# Schematic_WT-03_v_1_0.net
KiCad netlist of a schematic drawn in EasyEDA
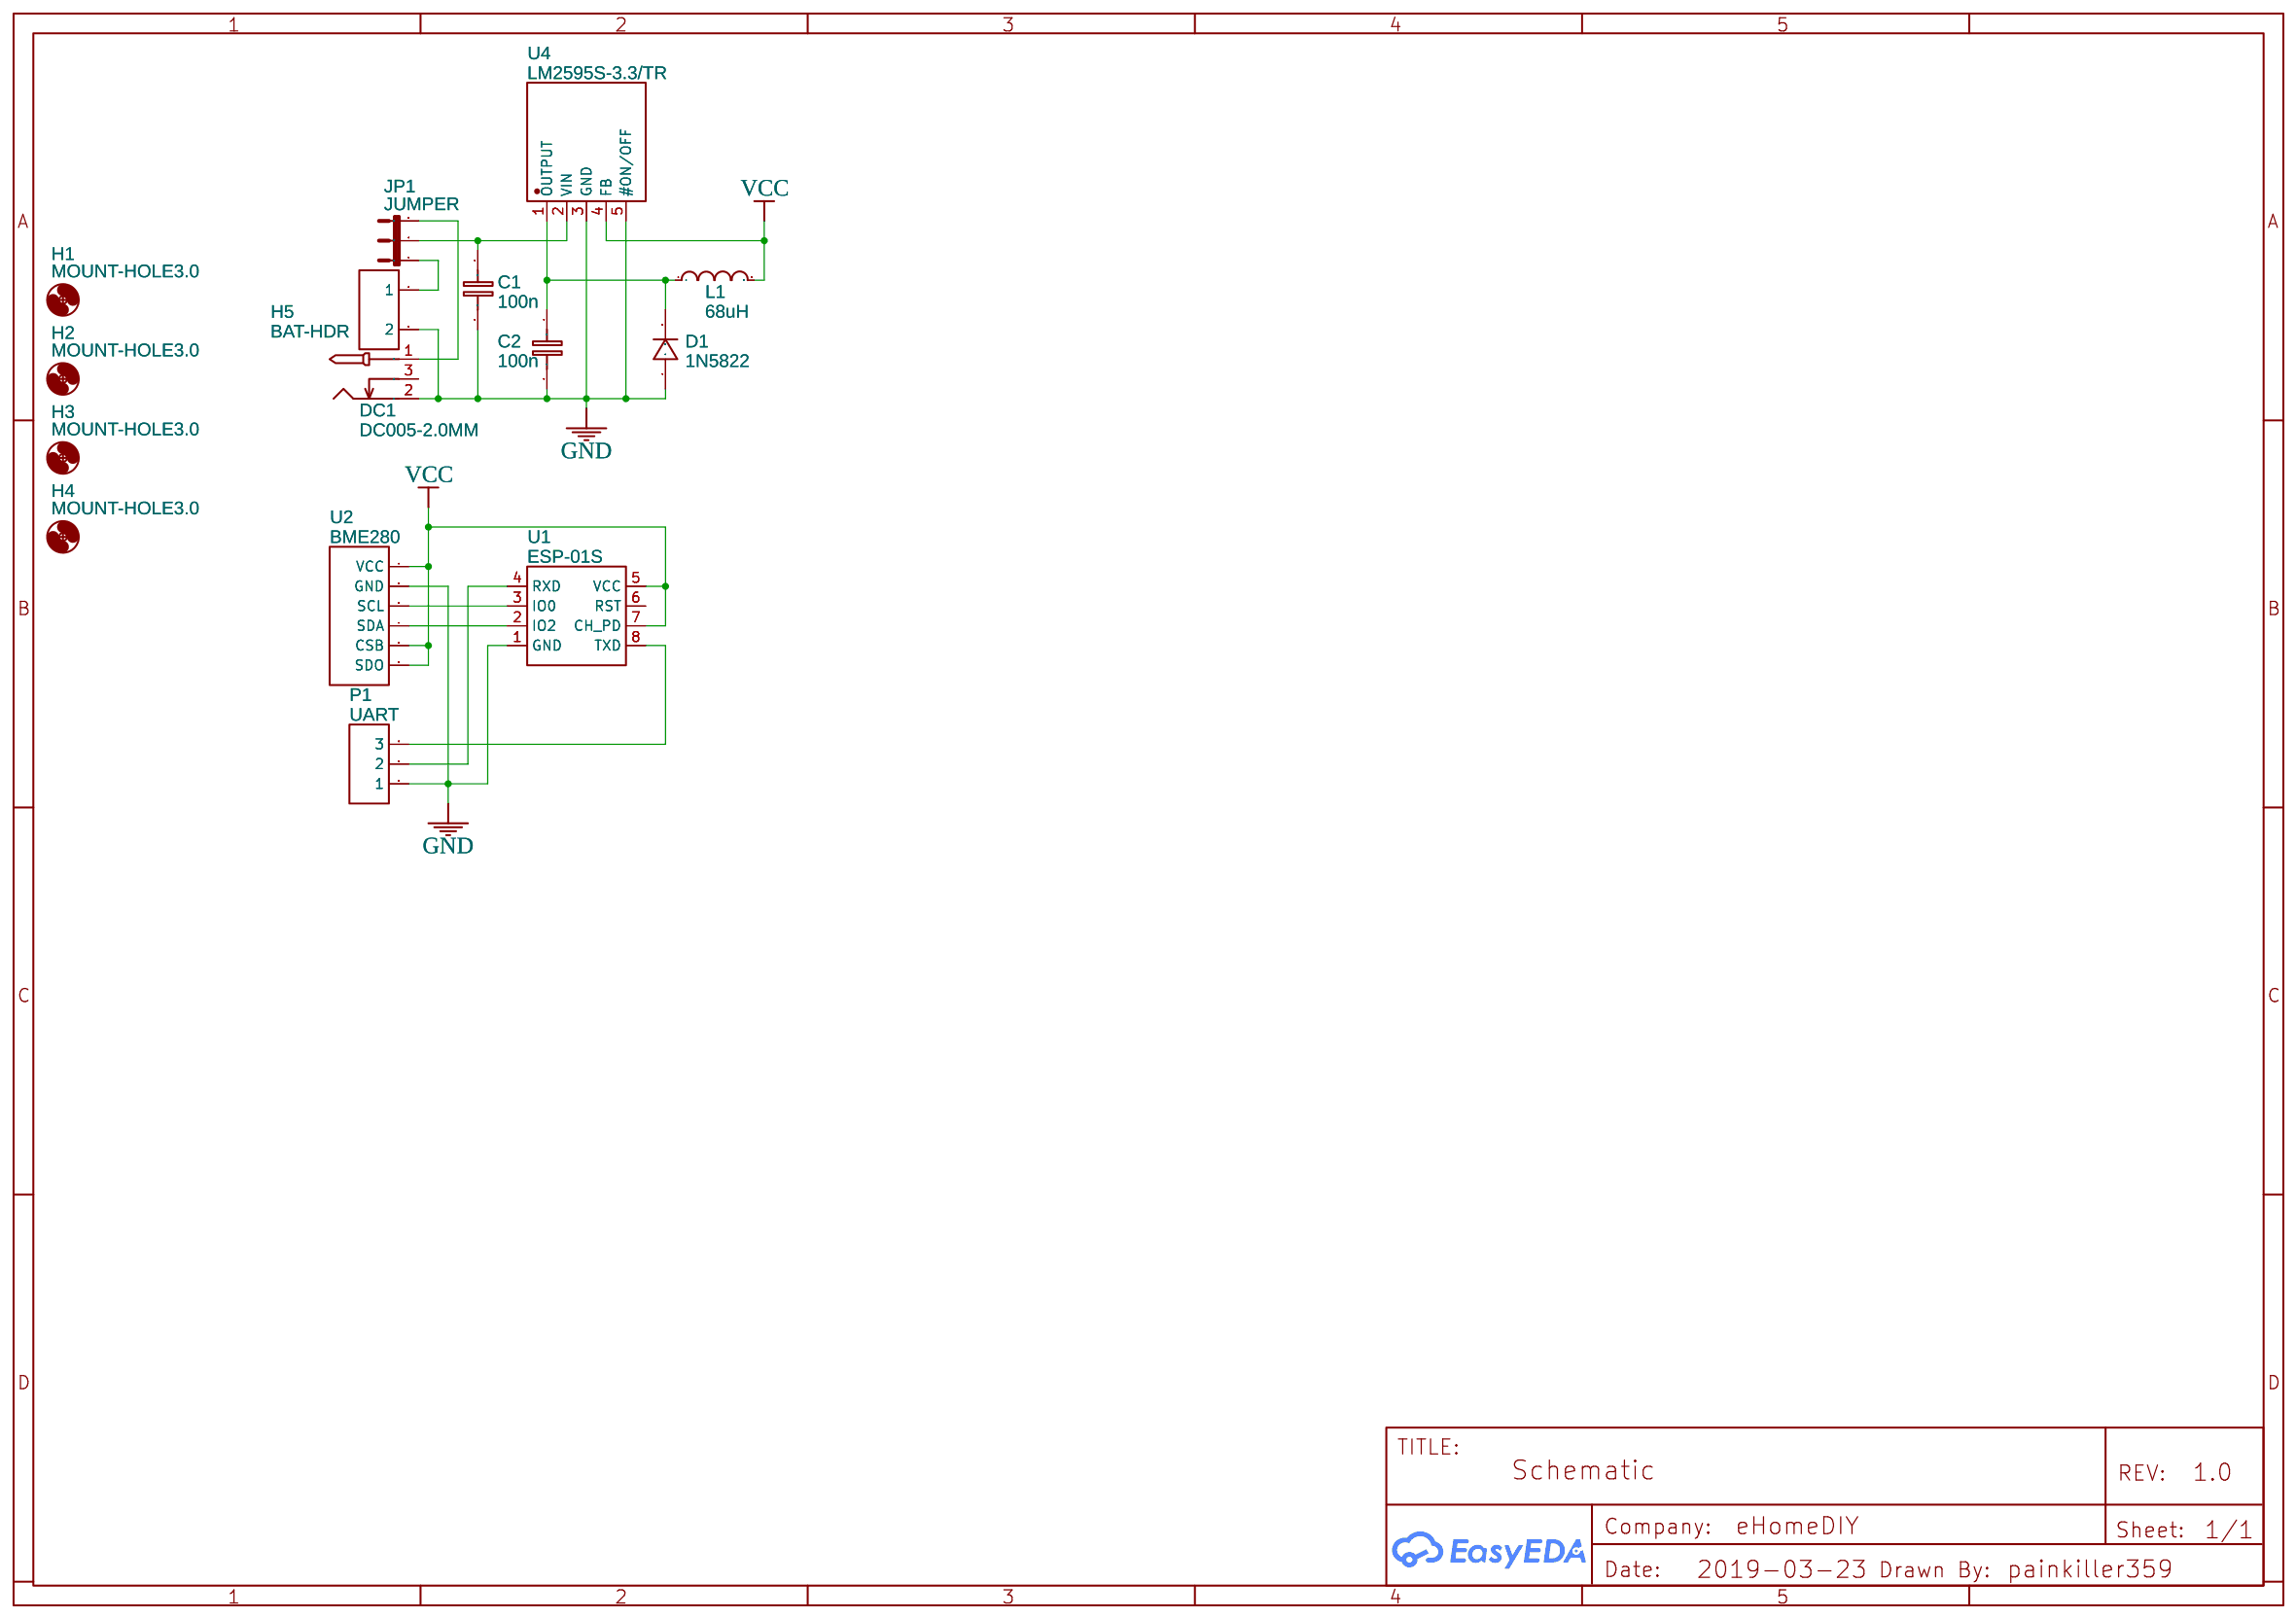
[diagram p0: schematic sheet]

(export (version "E")
  (design (tool "Eeschema 10.0.6"))
  (components
    (comp (ref "C1")
      (value "100n")
      (fields (field (name "BOM_Manufacturer Part") "?"))
      (libsource (lib "") (part "Cap_RAD-0.1_EU"))
    )
    (comp (ref "C2")
      (value "100n")
      (fields (field (name "BOM_Manufacturer Part") "?"))
      (libsource (lib "") (part "Cap_RAD-0.1_EU"))
    )
    (comp (ref "D1")
      (value "1N5822")
      (fields (field (name "BOM_Supplier Part") "C169161"))
      (libsource (lib "") (part "Unknown_330_170"))
    )
    (comp (ref "DC1")
      (value "DC005-2.0MM")
      (fields (field (name "BOM_Supplier Part") "C111567"))
      (libsource (lib "") (part "Unknown_185_180"))
    )
    (comp (ref "H1")
      (value "MOUNT-HOLE3.0")
      (fields (field (name "BOM_Manufacturer Part") "?"))
      (libsource (lib "") (part "Unknown_25_145"))
    )
    (comp (ref "H2")
      (value "MOUNT-HOLE3.0")
      (fields (field (name "BOM_Manufacturer Part") "?"))
      (libsource (lib "") (part "Unknown_25_185"))
    )
    (comp (ref "H3")
      (value "MOUNT-HOLE3.0")
      (fields (field (name "BOM_Manufacturer Part") "?"))
      (libsource (lib "") (part "Unknown_25_225"))
    )
    (comp (ref "H4")
      (value "MOUNT-HOLE3.0")
      (fields (field (name "BOM_Manufacturer Part") "?"))
      (libsource (lib "") (part "Unknown_25_265"))
    )
    (comp (ref "H5")
      (value "BAT-HDR")
      (fields (field (name "BOM_Manufacturer Part") "826629-2") (field (name "BOM_Supplier Part") "C86471"))
      (libsource (lib "") (part "Unknown_190_150"))
    )
    (comp (ref "JP1")
      (value "JUMPER")
      (fields (field (name "BOM_Manufacturer Part") "?"))
      (libsource (lib "") (part "Unknown_195_115"))
    )
    (comp (ref "L1")
      (value "68uH")
      (fields
        (field (name "BOM_Manufacturer Part") "VLU1012-680KB")
        (field (name "BOM_Supplier Part") "C142465")
      )
      (libsource (lib "") (part "VLU1012-680KB"))
    )
    (comp (ref "P1")
      (value "UART")
      (fields
        (field (name "BOM_Manufacturer Part") "Header2.54mm 1*3P")
        (field (name "BOM_Supplier Part") "C49257")
      )
      (libsource (lib "") (part "Unknown_185_380"))
    )
    (comp (ref "U1")
      (value "ESP-01S")
      (fields (field (name "BOM_Supplier Part") "C111009"))
      (libsource (lib "") (part "Unknown_285_305"))
    )
    (comp (ref "U2")
      (value "BME280")
      (fields (field (name "BOM_Manufacturer Part") "?") (field (name "BOM_Supplier Part") "GY-BME280"))
      (libsource (lib "") (part "Unknown_185_305"))
    )
    (comp (ref "U4")
      (value "LM2595S-3.3/TR")
      (fields (field (name "BOM_Supplier Part") "C316688"))
      (libsource (lib "") (part "Unknown_290_75"))
    )
  )
  (nets
    (net (code "1") (name "GND") (class "Default")
      (node (ref "C1") (pin "2") (pinfunction "2_2") (pintype "unspecified"))
      (node (ref "C2") (pin "2") (pinfunction "2_2") (pintype "unspecified"))
      (node (ref "D1") (pin "1") (pinfunction "1_1") (pintype "unspecified"))
      (node (ref "DC1") (pin "2") (pinfunction "2_2") (pintype "unspecified"))
      (node (ref "H5") (pin "2") (pinfunction "2_2") (pintype "unspecified"))
      (node (ref "P1") (pin "1") (pinfunction "1_1") (pintype "input"))
      (node (ref "U1") (pin "1") (pinfunction "GND_1") (pintype "unspecified"))
      (node (ref "U2") (pin "2") (pinfunction "GND_2") (pintype "input"))
      (node (ref "U4") (pin "3") (pinfunction "GND_3") (pintype "unspecified"))
      (node (ref "U4") (pin "5") (pinfunction "#ON/OFF_5") (pintype "unspecified"))
    )
    (net (code "2") (name "Net-(DC1-Pad1)") (class "Default")
      (node (ref "DC1") (pin "1") (pinfunction "1_1") (pintype "unspecified"))
      (node (ref "JP1") (pin "3") (pinfunction "3_3") (pintype "unspecified"))
    )
    (net (code "3") (name "Net-(H5-Pad1)") (class "Default")
      (node (ref "H5") (pin "1") (pinfunction "1_1") (pintype "unspecified"))
      (node (ref "JP1") (pin "1") (pinfunction "1_1") (pintype "unspecified"))
    )
    (net (code "4") (name "Net-(U1-IO0)") (class "Default")
      (node (ref "U1") (pin "3") (pinfunction "IO0_3") (pintype "unspecified"))
      (node (ref "U2") (pin "3") (pinfunction "SCL_3") (pintype "input"))
    )
    (net (code "5") (name "Net-(U1-IO2)") (class "Default")
      (node (ref "U1") (pin "2") (pinfunction "IO2_2") (pintype "unspecified"))
      (node (ref "U2") (pin "4") (pinfunction "SDA_4") (pintype "input"))
    )
    (net (code "6") (name "Net-(U1-RXD)") (class "Default")
      (node (ref "P1") (pin "2") (pinfunction "2_2") (pintype "input"))
      (node (ref "U1") (pin "4") (pinfunction "RXD_4") (pintype "unspecified"))
    )
    (net (code "7") (name "Net-(U1-TXD)") (class "Default")
      (node (ref "P1") (pin "3") (pinfunction "3_3") (pintype "input"))
      (node (ref "U1") (pin "8") (pinfunction "TXD_8") (pintype "unspecified"))
    )
    (net (code "8") (name "Net-(U4-OUTPUT)") (class "Default")
      (node (ref "C2") (pin "1") (pinfunction "1_1") (pintype "unspecified"))
      (node (ref "D1") (pin "2") (pinfunction "2_2") (pintype "unspecified"))
      (node (ref "L1") (pin "1") (pinfunction "1_1") (pintype "unspecified"))
      (node (ref "U4") (pin "1") (pinfunction "OUTPUT_1") (pintype "unspecified"))
    )
    (net (code "9") (name "Net-(U4-VIN)") (class "Default")
      (node (ref "C1") (pin "1") (pinfunction "1_1") (pintype "unspecified"))
      (node (ref "JP1") (pin "2") (pinfunction "2_2") (pintype "unspecified"))
      (node (ref "U4") (pin "2") (pinfunction "VIN_2") (pintype "unspecified"))
    )
    (net (code "10") (name "VCC") (class "Default")
      (node (ref "L1") (pin "2") (pinfunction "2_2") (pintype "unspecified"))
      (node (ref "U1") (pin "5") (pinfunction "VCC_5") (pintype "unspecified"))
      (node (ref "U1") (pin "7") (pinfunction "CH_PD_7") (pintype "unspecified"))
      (node (ref "U2") (pin "1") (pinfunction "VCC_1") (pintype "input"))
      (node (ref "U2") (pin "5") (pinfunction "CSB_5") (pintype "input"))
      (node (ref "U2") (pin "6") (pinfunction "SDO_6") (pintype "input"))
      (node (ref "U4") (pin "4") (pinfunction "FB_4") (pintype "unspecified"))
    )
    (net (code "11") (name "unconnected-(DC1-Pad3)") (class "Default")
      (node (ref "DC1") (pin "3") (pinfunction "3_3") (pintype "unspecified"))
    )
    (net (code "12") (name "unconnected-(U1-RST-Pad6)") (class "Default")
      (node (ref "U1") (pin "6") (pinfunction "RST_6") (pintype "unspecified"))
    )
  )
)
